# microcc.net
KiCad netlist of a schematic drawn in EAGLE
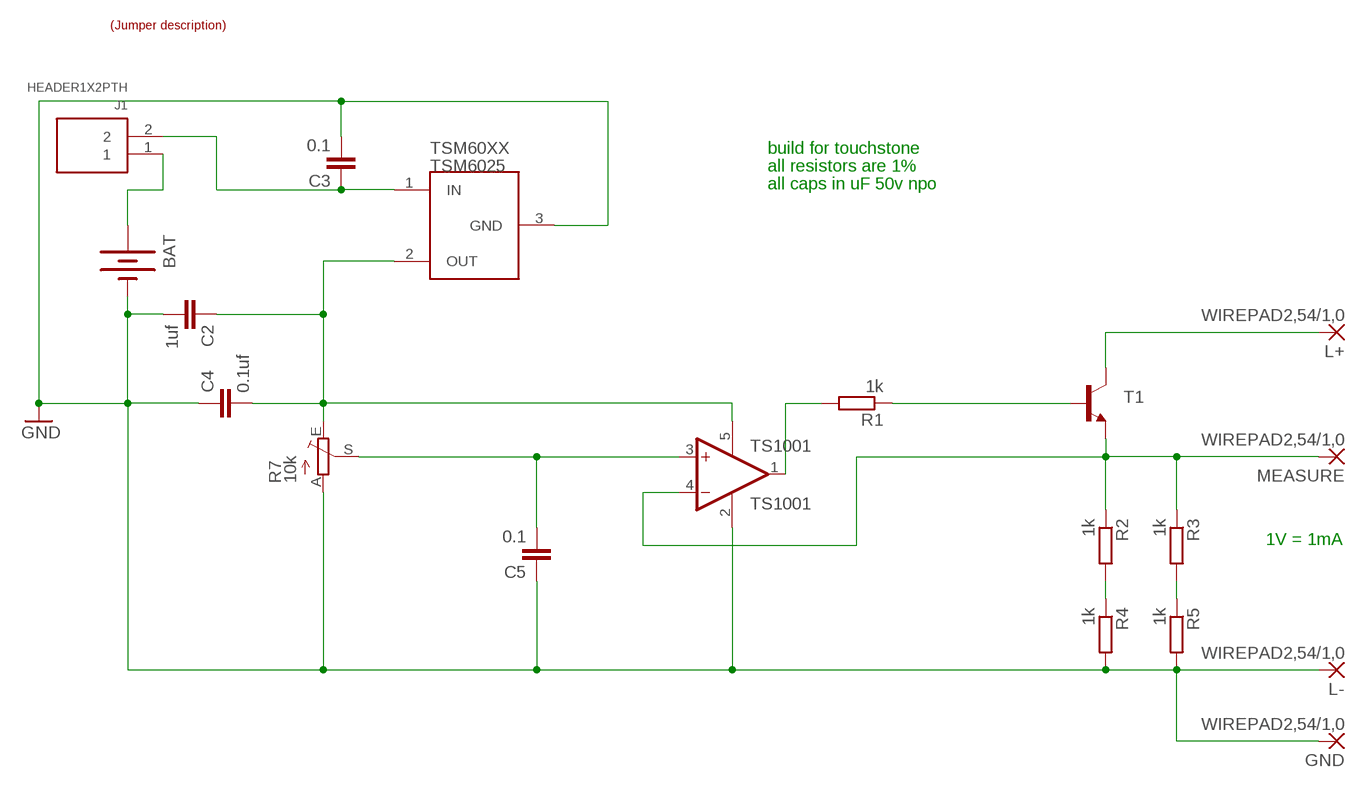
[diagram p0: schematic, sheet 1]

(export (version "E")
  (design (tool "Eeschema 10.0.6"))
  (components
    (comp (ref "BAT")
      (value "BATTERY20SMD")
      (footprint "eagle-import:BATTCON_20MM")
      (libsource (lib "eagle-import") (part "BATTERY20SMD"))
    )
    (comp (ref "C2")
      (value "1uf")
      (footprint "eagle-import:C603")
      (libsource (lib "eagle-import") (part "CAPC603"))
    )
    (comp (ref "C3")
      (value "0.1")
      (footprint "eagle-import:C603")
      (libsource (lib "eagle-import") (part "CAPC603"))
    )
    (comp (ref "C4")
      (value "0.1uf")
      (footprint "eagle-import:C603")
      (libsource (lib "eagle-import") (part "CAPC603"))
    )
    (comp (ref "C5")
      (value "0.1")
      (footprint "eagle-import:C603")
      (libsource (lib "eagle-import") (part "CAPC603"))
    )
    (comp (ref "GND")
      (value "WIREPAD2,54/1,0")
      (footprint "eagle-import:2,54_1,0")
      (libsource (lib "eagle-import") (part "WIREPAD2,54/1,0"))
    )
    (comp (ref "J1")
      (value "HEADER1X2PTH")
      (footprint "eagle-import:M1X2")
      (libsource (lib "eagle-import") (part "HEADER1X2PTH"))
    )
    (comp (ref "L+")
      (value "WIREPAD2,54/1,0")
      (footprint "eagle-import:2,54_1,0")
      (libsource (lib "eagle-import") (part "WIREPAD2,54/1,0"))
    )
    (comp (ref "L-")
      (value "WIREPAD2,54/1,0")
      (footprint "eagle-import:2,54_1,0")
      (libsource (lib "eagle-import") (part "WIREPAD2,54/1,0"))
    )
    (comp (ref "MEASURE")
      (value "WIREPAD2,54/1,0")
      (footprint "eagle-import:2,54_1,0")
      (libsource (lib "eagle-import") (part "WIREPAD2,54/1,0"))
    )
    (comp (ref "R1")
      (value "1k")
      (footprint "eagle-import:R603")
      (libsource (lib "eagle-import") (part "RESISTORR603"))
    )
    (comp (ref "R2")
      (value "1k")
      (footprint "eagle-import:R603")
      (libsource (lib "eagle-import") (part "RESISTORR603"))
    )
    (comp (ref "R3")
      (value "1k")
      (footprint "eagle-import:R603")
      (libsource (lib "eagle-import") (part "RESISTORR603"))
    )
    (comp (ref "R4")
      (value "1k")
      (footprint "eagle-import:R603")
      (libsource (lib "eagle-import") (part "RESISTORR603"))
    )
    (comp (ref "R5")
      (value "1k")
      (footprint "eagle-import:R603")
      (libsource (lib "eagle-import") (part "RESISTORR603"))
    )
    (comp (ref "R7")
      (value "10k")
      (footprint "eagle-import:PT-SPIN")
      (libsource (lib "eagle-import") (part "TRIM_EU-PTSPIN"))
    )
    (comp (ref "T1")
      (value "TRANSISTOR_NPNSOT23")
      (footprint "eagle-import:SOT23")
      (libsource (lib "eagle-import") (part "TRANSISTOR_NPNSOT23"))
    )
    (comp (ref "TS1001")
      (value "TS1001")
      (footprint "eagle-import:SC70-5L")
      (libsource (lib "eagle-import") (part "TS1001"))
    )
    (comp (ref "TSM6025")
      (value "TSM60XX")
      (footprint "eagle-import:SOT23")
      (libsource (lib "eagle-import") (part "TSM60XX"))
    )
    (comp (ref "U$1")
      (value "JUMP2_DESC")
      (footprint "eagle-import:JUMP2_DESC")
      (libsource (lib "eagle-import") (part "JUMP2_DESC"))
    )
  )
  (nets
    (net (code "1") (name "GND") (class "Default")
      (node (ref "BAT") (pin "2") (pinfunction "-_2") (pintype "power_in"))
      (node (ref "C2") (pin "2") (pinfunction "2_2") (pintype "passive"))
      (node (ref "C3") (pin "2") (pinfunction "2_2") (pintype "passive"))
      (node (ref "C4") (pin "1") (pinfunction "1_1") (pintype "passive"))
      (node (ref "C5") (pin "1") (pinfunction "1_1") (pintype "passive"))
      (node (ref "GND") (pin "1") (pinfunction "P_1") (pintype "passive"))
      (node (ref "L-") (pin "1") (pinfunction "P_1") (pintype "passive"))
      (node (ref "R4") (pin "2") (pinfunction "2_2") (pintype "passive"))
      (node (ref "R5") (pin "2") (pinfunction "2_2") (pintype "passive"))
      (node (ref "R7") (pin "A") (pinfunction "A_A") (pintype "passive"))
      (node (ref "TS1001") (pin "2") (pinfunction "V-_2") (pintype "power_in"))
      (node (ref "TSM6025") (pin "3") (pinfunction "GND_3") (pintype "bidirectional"))
    )
    (net (code "2") (name "Net-(BAT-+)") (class "Default")
      (node (ref "BAT") (pin "1") (pinfunction "+_1") (pintype "power_in"))
      (node (ref "J1") (pin "1") (pinfunction "1_1") (pintype "bidirectional"))
    )
    (net (code "3") (name "Net-(L+-P)") (class "Default")
      (node (ref "L+") (pin "1") (pinfunction "P_1") (pintype "passive"))
      (node (ref "T1") (pin "3") (pinfunction "C_3") (pintype "passive"))
    )
    (net (code "4") (name "Net-(MEASURE-P)") (class "Default")
      (node (ref "MEASURE") (pin "1") (pinfunction "P_1") (pintype "passive"))
      (node (ref "R2") (pin "1") (pinfunction "1_1") (pintype "passive"))
      (node (ref "R3") (pin "1") (pinfunction "1_1") (pintype "passive"))
      (node (ref "T1") (pin "2") (pinfunction "E_2") (pintype "passive"))
      (node (ref "TS1001") (pin "4") (pinfunction "-IN_4") (pintype "input"))
    )
    (net (code "5") (name "Net-(R2-Pad2)") (class "Default")
      (node (ref "R2") (pin "2") (pinfunction "2_2") (pintype "passive"))
      (node (ref "R4") (pin "1") (pinfunction "1_1") (pintype "passive"))
    )
    (net (code "6") (name "Net-(R3-Pad2)") (class "Default")
      (node (ref "R3") (pin "2") (pinfunction "2_2") (pintype "passive"))
      (node (ref "R5") (pin "1") (pinfunction "1_1") (pintype "passive"))
    )
    (net (code "7") (name "Net-(T1-B)") (class "Default")
      (node (ref "R1") (pin "1") (pinfunction "1_1") (pintype "passive"))
      (node (ref "T1") (pin "1") (pinfunction "B_1") (pintype "passive"))
    )
    (net (code "8") (name "Net-(TS1001-+IN)") (class "Default")
      (node (ref "C5") (pin "2") (pinfunction "2_2") (pintype "passive"))
      (node (ref "R7") (pin "S") (pinfunction "S_S") (pintype "passive"))
      (node (ref "TS1001") (pin "3") (pinfunction "+IN_3") (pintype "input"))
    )
    (net (code "9") (name "Net-(TS1001-OUT)") (class "Default")
      (node (ref "R1") (pin "2") (pinfunction "2_2") (pintype "passive"))
      (node (ref "TS1001") (pin "1") (pinfunction "OUT_1") (pintype "output"))
    )
    (net (code "10") (name "Net-(TS1001-V+)") (class "Default")
      (node (ref "C2") (pin "1") (pinfunction "1_1") (pintype "passive"))
      (node (ref "C4") (pin "2") (pinfunction "2_2") (pintype "passive"))
      (node (ref "R7") (pin "E") (pinfunction "E_E") (pintype "passive"))
      (node (ref "TS1001") (pin "5") (pinfunction "V+_5") (pintype "power_in"))
      (node (ref "TSM6025") (pin "2") (pinfunction "OUT_2") (pintype "bidirectional"))
    )
    (net (code "11") (name "Net-(TSM6025-IN)") (class "Default")
      (node (ref "C3") (pin "1") (pinfunction "1_1") (pintype "passive"))
      (node (ref "J1") (pin "2") (pinfunction "2_2") (pintype "bidirectional"))
      (node (ref "TSM6025") (pin "1") (pinfunction "IN_1") (pintype "bidirectional"))
    )
  )
)
